# Tachometr.net
KiCad netlist of a schematic drawn in EAGLE
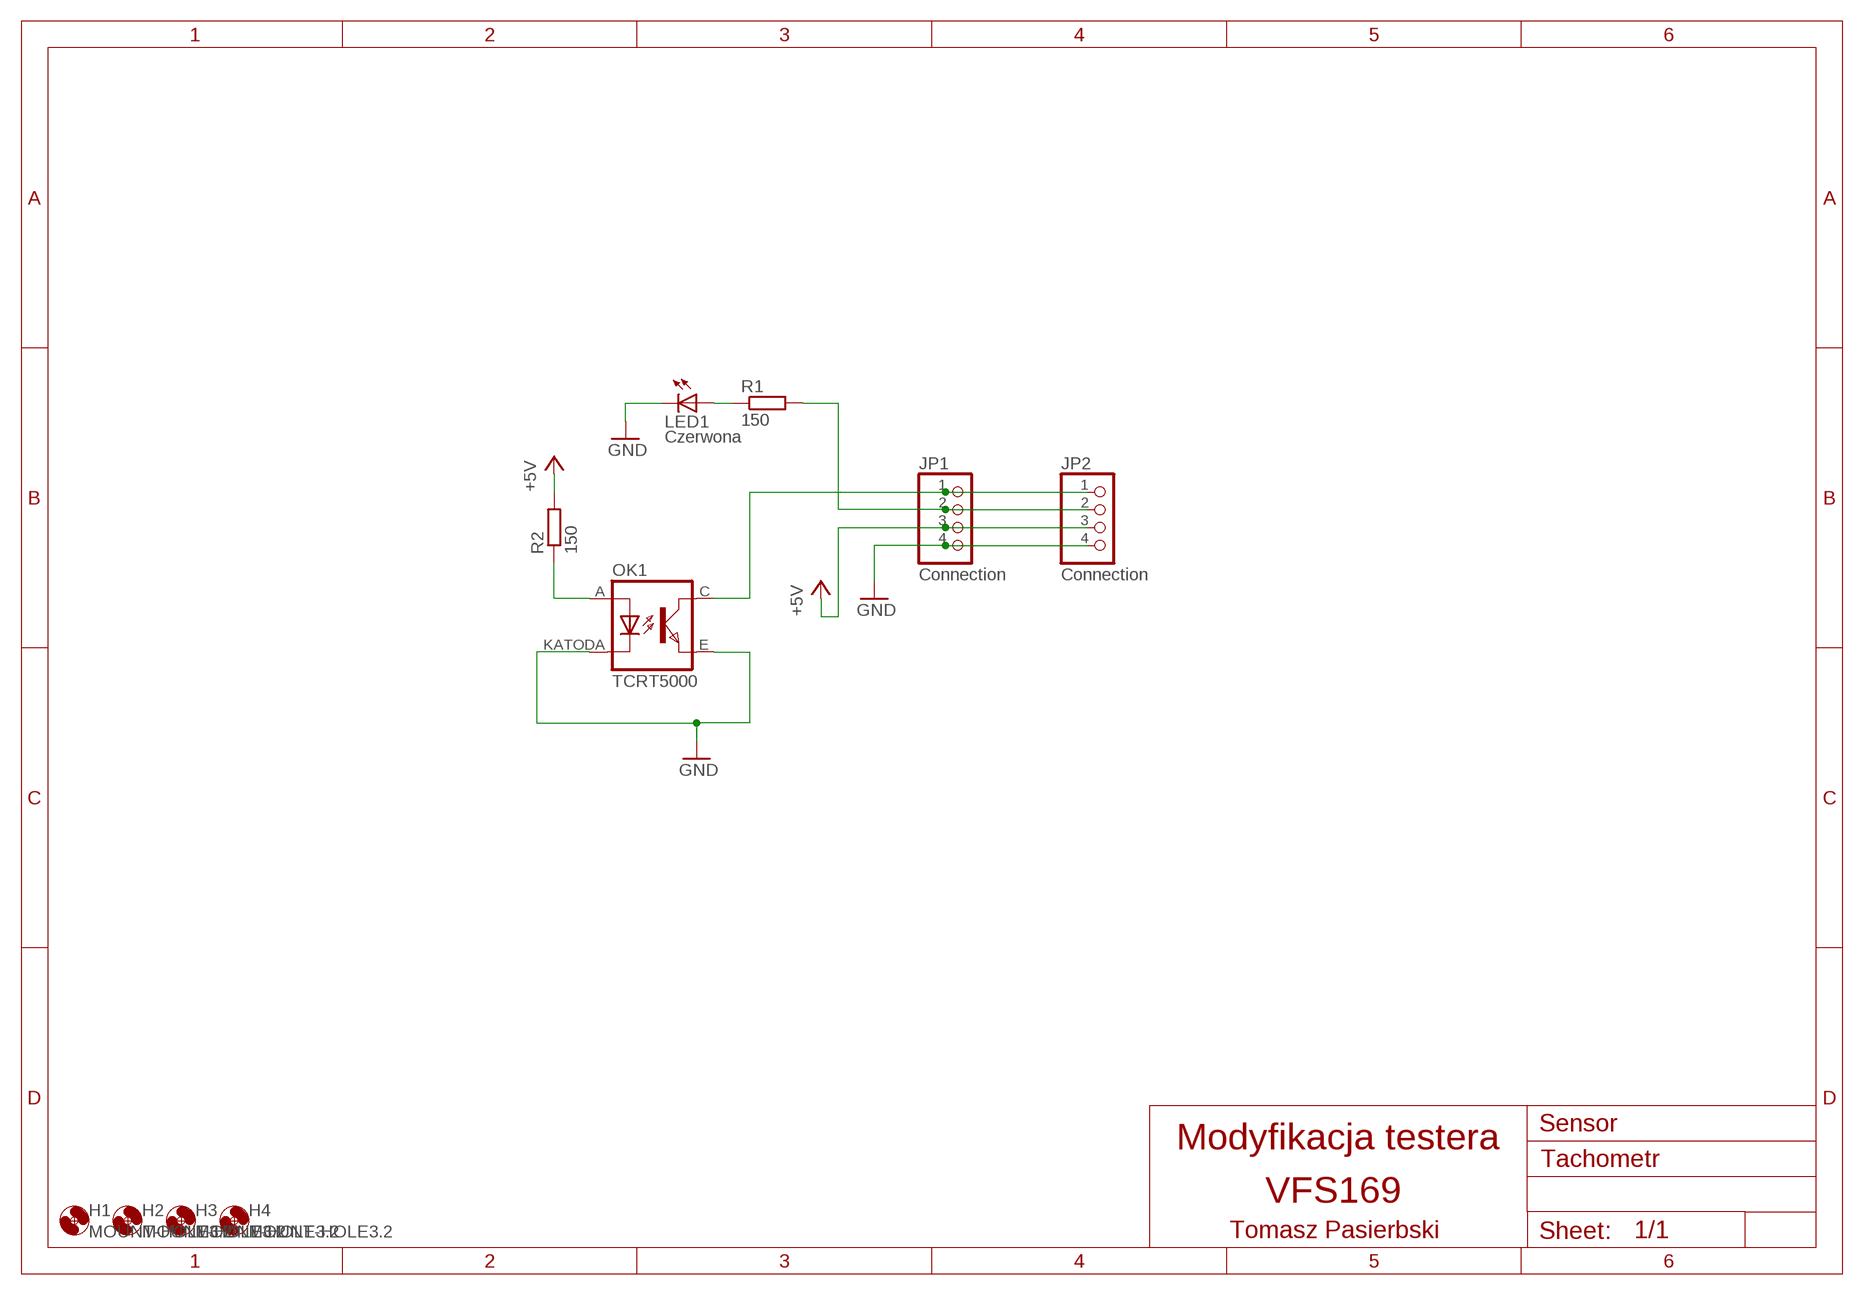
[diagram p0: schematic, sheet 1]

(export (version "E")
  (design (tool "Eeschema 10.0.6"))
  (components
    (comp (ref "H1")
      (value "MOUNT-HOLE3.2")
      (footprint "eagle-import:3,2")
      (libsource (lib "eagle-import") (part "MOUNT-HOLE3.2"))
    )
    (comp (ref "H2")
      (value "MOUNT-HOLE3.2")
      (footprint "eagle-import:3,2")
      (libsource (lib "eagle-import") (part "MOUNT-HOLE3.2"))
    )
    (comp (ref "H3")
      (value "MOUNT-HOLE3.2")
      (footprint "eagle-import:3,2")
      (libsource (lib "eagle-import") (part "MOUNT-HOLE3.2"))
    )
    (comp (ref "H4")
      (value "MOUNT-HOLE3.2")
      (footprint "eagle-import:3,2")
      (libsource (lib "eagle-import") (part "MOUNT-HOLE3.2"))
    )
    (comp (ref "JP1")
      (value "Connection")
      (footprint "eagle-import:1X04_90")
      (libsource (lib "eagle-import") (part "PINHD-1X4/90"))
    )
    (comp (ref "JP2")
      (value "Connection")
      (footprint "eagle-import:1X04")
      (libsource (lib "eagle-import") (part "PINHD-1X4"))
    )
    (comp (ref "LED1")
      (value "Czerwona")
      (footprint "eagle-import:CHIPLED_1206")
      (libsource (lib "eagle-import") (part "LEDCHIPLED_1206"))
    )
    (comp (ref "OK1")
      (value "TCRT5000")
      (footprint "eagle-import:TCRT5000")
      (libsource (lib "eagle-import") (part "TCRT5000"))
    )
    (comp (ref "R1")
      (value "150")
      (footprint "eagle-import:R1206")
      (libsource (lib "eagle-import") (part "R-EU_R1206"))
    )
    (comp (ref "R2")
      (value "150")
      (footprint "eagle-import:R1206")
      (libsource (lib "eagle-import") (part "R-EU_R1206"))
    )
  )
  (nets
    (net (code "1") (name "+5V") (class "Default")
      (node (ref "JP1") (pin "3") (pinfunction "3_3") (pintype "passive"))
      (node (ref "JP2") (pin "3") (pinfunction "3_3") (pintype "passive"))
      (node (ref "R2") (pin "2") (pinfunction "2_2") (pintype "passive"))
    )
    (net (code "2") (name "GND") (class "Default")
      (node (ref "JP1") (pin "4") (pinfunction "4_4") (pintype "passive"))
      (node (ref "JP2") (pin "4") (pinfunction "4_4") (pintype "passive"))
      (node (ref "LED1") (pin "C") (pinfunction "C_C") (pintype "passive"))
      (node (ref "OK1") (pin "E") (pinfunction "EMITTER_E") (pintype "passive"))
      (node (ref "OK1") (pin "KATODA") (pinfunction "CATHODE_KATODA") (pintype "passive"))
    )
    (net (code "3") (name "Net-(JP1-Pad2)") (class "Default")
      (node (ref "JP1") (pin "2") (pinfunction "2_2") (pintype "passive"))
      (node (ref "JP2") (pin "2") (pinfunction "2_2") (pintype "passive"))
      (node (ref "R1") (pin "2") (pinfunction "2_2") (pintype "passive"))
    )
    (net (code "4") (name "Net-(LED1-PadA)") (class "Default")
      (node (ref "LED1") (pin "A") (pinfunction "A_A") (pintype "passive"))
      (node (ref "R1") (pin "1") (pinfunction "1_1") (pintype "passive"))
    )
    (net (code "5") (name "Net-(OK1-ANODE)") (class "Default")
      (node (ref "OK1") (pin "A") (pinfunction "ANODE_A") (pintype "passive"))
      (node (ref "R2") (pin "1") (pinfunction "1_1") (pintype "passive"))
    )
    (net (code "6") (name "Net-(OK1-COLLECTOR)") (class "Default")
      (node (ref "JP1") (pin "1") (pinfunction "1_1") (pintype "passive"))
      (node (ref "JP2") (pin "1") (pinfunction "1_1") (pintype "passive"))
      (node (ref "OK1") (pin "C") (pinfunction "COLLECTOR_C") (pintype "passive"))
    )
  )
)
